# CameraSupplies.net
KiCad netlist of a schematic drawn in Altium Designer
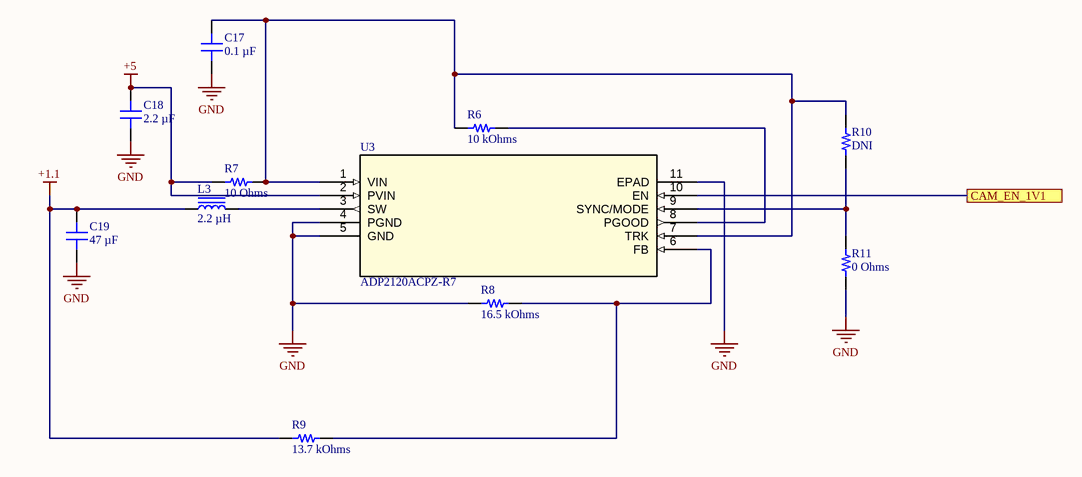
[diagram p0: CameraSupplies.SchDoc]

(export (version "E")
  (design (tool "Eeschema 10.0.6"))
  (components
    (comp (ref "C17")
      (value "0.1 µF")
      (footprint "CAP 0201_0603")
      (description "CAP CER 0.1UF 10V X5R 0201")
      (fields
        (field (name "PART NUMBER") "GRM033R61A104KE15D")
        (field (name "MANUFACTURER") "Murata Electronics")
      )
      (libsource (lib "Celestial Altium Library - altium_library") (part "Capacitor"))
    )
    (comp (ref "C18")
      (value "2.2 µF")
      (footprint "CAP 0402_1005")
      (description "CAP CER 2.2UF 16V X5R 0402")
      (fields
        (field (name "PART NUMBER") "GRM155R61C225ME44D")
        (field (name "MANUFACTURER") "Murata Electronics")
      )
      (libsource (lib "Celestial Altium Library - altium_library") (part "Capacitor"))
    )
    (comp (ref "C19")
      (value "47 µF")
      (footprint "CAP 0603_1608")
      (description "CAP CER 47UF 6.3V X5R 0603")
      (fields
        (field (name "PART NUMBER") "GRM188R60J476ME01D")
        (field (name "MANUFACTURER") "Murata Electronics")
      )
      (libsource (lib "Celestial Altium Library - altium_library") (part "Capacitor"))
    )
    (comp (ref "L3")
      (value "2.2 µH")
      (footprint "IND 0806_2016")
      (description "FIXED IND 2.2UH 1.6A 135MOHM SMD")
      (fields (field (name "PART NUMBER") "74479276222C") (field (name "MANUFACTURER") "Würth Elektronik"))
      (libsource (lib "Celestial Altium Library - altium_library") (part "Inductor"))
    )
    (comp (ref "R6")
      (value "10 kOhms")
      (footprint "RES 0201_0603")
      (description "RES SMD 10K OHM 1% 1/20W 0201")
      (fields (field (name "PART NUMBER") "CRCW020110K0FKED") (field (name "MANUFACTURER") "Vishay Dale"))
      (libsource (lib "Celestial Altium Library - altium_library") (part "Resistor"))
    )
    (comp (ref "R7")
      (value "10 Ohms")
      (footprint "RES 0201_0603")
      (description "RES SMD 10 OHM 1% 1/20W 0201")
      (fields
        (field (name "PART NUMBER") "CRG0201F10R")
        (field (name "MANUFACTURER") "TE Connectivity Passive Product")
      )
      (libsource (lib "Celestial Altium Library - altium_library") (part "Resistor"))
    )
    (comp (ref "R8")
      (value "16.5 kOhms")
      (footprint "RES 0201_0603")
      (description "RES SMD 16.5K OHM 1% 1/20W 0201")
      (fields (field (name "PART NUMBER") "CRCW020116K5FNED") (field (name "MANUFACTURER") "Vishay Dale"))
      (libsource (lib "Celestial Altium Library - altium_library") (part "Resistor"))
    )
    (comp (ref "R9")
      (value "13.7 kOhms")
      (footprint "RES 0201_0603")
      (description "RES 13.7K OHM 1% 1/20W 0201")
      (fields
        (field (name "PART NUMBER") "RK73H1HTTC1372F")
        (field (name "MANUFACTURER") "KOA Speer Electronics, Inc.")
      )
      (libsource (lib "Celestial Altium Library - altium_library") (part "Resistor"))
    )
    (comp (ref "R10")
      (value "DNI")
      (footprint "RES 0402_1005")
      (description "RES SMD 0 OHM JUMPER 1/5W 0402")
      (fields (field (name "PART NUMBER") "CRCW04020000Z0EDHP") (field (name "MANUFACTURER") "Vishay Dale"))
      (libsource (lib "Celestial Altium Library - altium_library") (part "Resistor"))
    )
    (comp (ref "R11")
      (value "0 Ohms")
      (footprint "RES 0402_1005")
      (description "RES SMD 0 OHM JUMPER 1/5W 0402")
      (fields (field (name "PART NUMBER") "CRCW04020000Z0EDHP") (field (name "MANUFACTURER") "Vishay Dale"))
      (libsource (lib "Celestial Altium Library - altium_library") (part "Resistor"))
    )
    (comp (ref "U3")
      (value "ADP2120ACPZ-R7")
      (footprint "CP_10_9_ADI")
      (description "No Description Available")
      (fields (field (name "COPYRIGHT") "Copyright (C) 2022 Ultra Librarian. All rights reserved."))
      (libsource (lib "SimulaVR") (part "ADP2120ACPZ-R7"))
    )
  )
  (nets
    (net (code "1") (name "+1.1") (class "Default")
      (node (ref "C19") (pin "2") (pinfunction "2_2") (pintype "passive"))
      (node (ref "L3") (pin "1") (pinfunction "1_1") (pintype "passive"))
      (node (ref "R9") (pin "1") (pinfunction "1_1") (pintype "passive"))
    )
    (net (code "2") (name "+5") (class "Default")
      (node (ref "C18") (pin "2") (pinfunction "2_2") (pintype "passive"))
      (node (ref "R7") (pin "1") (pinfunction "1_1") (pintype "passive"))
      (node (ref "U3") (pin "2") (pinfunction "PVIN_2") (pintype "input"))
    )
    (net (code "3") (name "/CAM_EN_1V1") (class "Default")
      (node (ref "U3") (pin "10") (pinfunction "EN_10") (pintype "input"))
    )
    (net (code "4") (name "GND") (class "Default")
      (node (ref "C17") (pin "1") (pinfunction "1_1") (pintype "passive"))
      (node (ref "C18") (pin "1") (pinfunction "1_1") (pintype "passive"))
      (node (ref "C19") (pin "1") (pinfunction "1_1") (pintype "passive"))
      (node (ref "R11") (pin "2") (pinfunction "2_2") (pintype "passive"))
      (node (ref "R8") (pin "1") (pinfunction "1_1") (pintype "passive"))
      (node (ref "U3") (pin "11") (pinfunction "EPAD_11") (pintype "passive"))
      (node (ref "U3") (pin "4") (pinfunction "PGND_4") (pintype "power_in"))
      (node (ref "U3") (pin "5") (pinfunction "GND_5") (pintype "power_in"))
    )
    (net (code "5") (name "Net-(U3-FB)") (class "Default")
      (node (ref "R8") (pin "2") (pinfunction "2_2") (pintype "passive"))
      (node (ref "R9") (pin "2") (pinfunction "2_2") (pintype "passive"))
      (node (ref "U3") (pin "6") (pinfunction "FB_6") (pintype "input"))
    )
    (net (code "6") (name "Net-(U3-PGOOD)") (class "Default")
      (node (ref "R6") (pin "2") (pinfunction "2_2") (pintype "passive"))
      (node (ref "U3") (pin "8") (pinfunction "PGOOD_8") (pintype "output"))
    )
    (net (code "7") (name "Net-(U3-SW)") (class "Default")
      (node (ref "L3") (pin "2") (pinfunction "2_2") (pintype "passive"))
      (node (ref "U3") (pin "3") (pinfunction "SW_3") (pintype "output"))
    )
    (net (code "8") (name "Net-(U3-SYNC{slash}MODE)") (class "Default")
      (node (ref "R10") (pin "2") (pinfunction "2_2") (pintype "passive"))
      (node (ref "R11") (pin "1") (pinfunction "1_1") (pintype "passive"))
      (node (ref "U3") (pin "9") (pinfunction "SYNC/MODE_9") (pintype "input"))
    )
    (net (code "9") (name "Net-(U3-TRK)") (class "Default")
      (node (ref "C17") (pin "2") (pinfunction "2_2") (pintype "passive"))
      (node (ref "R10") (pin "1") (pinfunction "1_1") (pintype "passive"))
      (node (ref "R6") (pin "1") (pinfunction "1_1") (pintype "passive"))
      (node (ref "R7") (pin "2") (pinfunction "2_2") (pintype "passive"))
      (node (ref "U3") (pin "1") (pinfunction "VIN_1") (pintype "input"))
      (node (ref "U3") (pin "7") (pinfunction "TRK_7") (pintype "input"))
    )
  )
)
